# wheelBLE.net
KiCad netlist of a schematic drawn in EAGLE
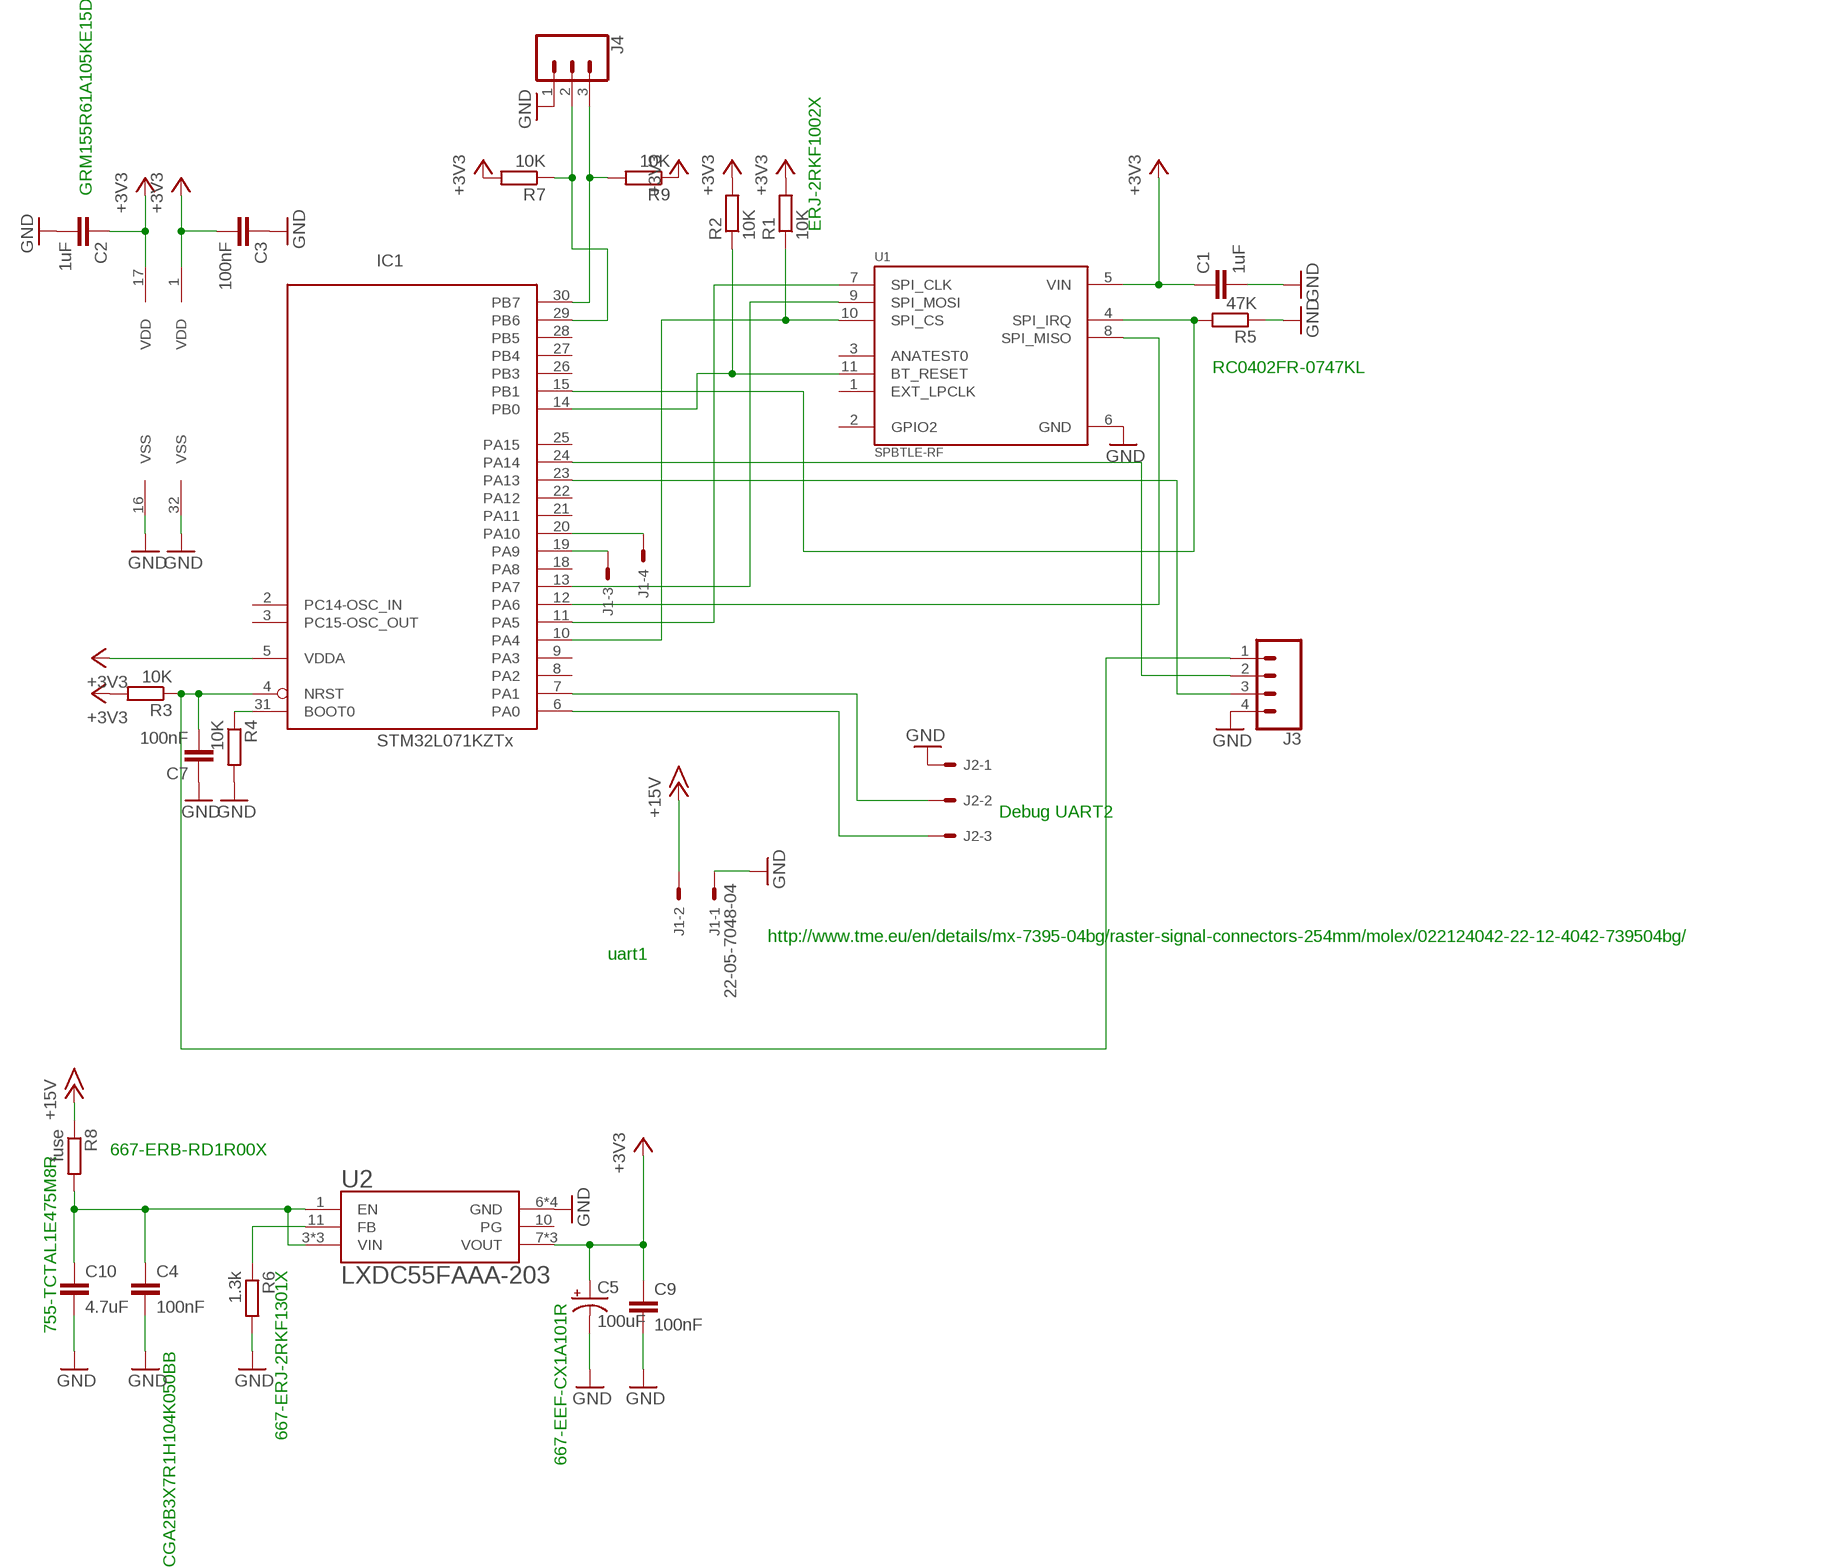
[diagram p0: schematic, sheet 1]

(export (version "E")
  (design (tool "Eeschema 10.0.6"))
  (components
    (comp (ref "C1")
      (value "1uF")
      (footprint "eagle-import:C0402")
      (libsource (lib "eagle-import") (part "C-EUC0402"))
    )
    (comp (ref "C2")
      (value "1uF")
      (footprint "eagle-import:C0402")
      (libsource (lib "eagle-import") (part "C-EUC0402"))
    )
    (comp (ref "C3")
      (value "100nF")
      (footprint "eagle-import:C0402")
      (libsource (lib "eagle-import") (part "C-EUC0402"))
    )
    (comp (ref "C4")
      (value "100nF")
      (footprint "eagle-import:C0402")
      (libsource (lib "eagle-import") (part "C-EUC0402"))
    )
    (comp (ref "C5")
      (value "100uF")
      (footprint "eagle-import:EIA7343")
      (libsource (lib "eagle-import") (part "100UF-POLAR-EIA7343-10V-10%(TANT)"))
    )
    (comp (ref "C7")
      (value "100nF")
      (footprint "eagle-import:C0402")
      (libsource (lib "eagle-import") (part "C-EUC0402"))
    )
    (comp (ref "C9")
      (value "100nF")
      (footprint "eagle-import:C0402")
      (libsource (lib "eagle-import") (part "C-EUC0402"))
    )
    (comp (ref "C10")
      (value "4.7uF")
      (footprint "eagle-import:1206")
      (libsource (lib "eagle-import") (part "4.7UF-1206-16V-(+80/-20%)"))
    )
    (comp (ref "IC1")
      (value "STM32L071KZTx")
      (footprint "eagle-import:LQFP32")
      (libsource (lib "eagle-import") (part "STM32L051KT8"))
    )
    (comp (ref "J1")
      (value "22-05-7048-04")
      (footprint "eagle-import:7395-04")
      (libsource (lib "eagle-import") (part "22-?-0405-7048"))
    )
    (comp (ref "J2")
      (value "22-05-7038-03")
      (footprint "eagle-import:7395-03")
      (libsource (lib "eagle-import") (part "22-?-0305-7038"))
    )
    (comp (ref "J3")
      (value "CONN_04")
      (footprint "eagle-import:1X04")
      (libsource (lib "eagle-import") (part "CONN_04"))
    )
    (comp (ref "J4")
      (value "CONN_03SMD")
      (footprint "eagle-import:1X03-1MM-RA")
      (libsource (lib "eagle-import") (part "CONN_03SMD"))
    )
    (comp (ref "R1")
      (value "10K")
      (footprint "eagle-import:R0402")
      (libsource (lib "eagle-import") (part "R-EU_R0402"))
    )
    (comp (ref "R2")
      (value "10K")
      (footprint "eagle-import:R0402")
      (libsource (lib "eagle-import") (part "R-EU_R0402"))
    )
    (comp (ref "R3")
      (value "10K")
      (footprint "eagle-import:R0402")
      (libsource (lib "eagle-import") (part "R-EU_R0402"))
    )
    (comp (ref "R4")
      (value "10K")
      (footprint "eagle-import:R0402")
      (libsource (lib "eagle-import") (part "R-EU_R0402"))
    )
    (comp (ref "R5")
      (value "47K")
      (footprint "eagle-import:R0402")
      (libsource (lib "eagle-import") (part "R-EU_R0402"))
    )
    (comp (ref "R6")
      (value "1.3k")
      (footprint "eagle-import:R0402")
      (libsource (lib "eagle-import") (part "R-EU_R0402"))
    )
    (comp (ref "R7")
      (value "10K")
      (footprint "eagle-import:R0402")
      (libsource (lib "eagle-import") (part "R-EU_R0402"))
    )
    (comp (ref "R8")
      (value "fuse")
      (footprint "eagle-import:R0402")
      (libsource (lib "eagle-import") (part "R-EU_R0402"))
    )
    (comp (ref "R9")
      (value "10K")
      (footprint "eagle-import:R0402")
      (libsource (lib "eagle-import") (part "R-EU_R0402"))
    )
    (comp (ref "U1")
      (value "SPBTLE-RF")
      (footprint "eagle-import:XCVR_SPBTLE-RF")
      (fields (field (name "MF") "STMicroelectronics"))
      (libsource (lib "eagle-import") (part "SPBTLE-RF"))
    )
    (comp (ref "U2")
      (value "LXDC55FAAA-203")
      (footprint "eagle-import:CONV_LXDC55FAAA-203")
      (fields (field (name "MF") "Murata"))
      (libsource (lib "eagle-import") (part "LXDC55FAAA-203"))
    )
  )
  (nets
    (net (code "1") (name "+3V3") (class "Default")
      (node (ref "C1") (pin "1") (pinfunction "1_1") (pintype "passive"))
      (node (ref "C2") (pin "1") (pinfunction "1_1") (pintype "passive"))
      (node (ref "C3") (pin "2") (pinfunction "2_2") (pintype "passive"))
      (node (ref "C5") (pin "A") (pinfunction "+_A") (pintype "passive"))
      (node (ref "C9") (pin "1") (pinfunction "1_1") (pintype "passive"))
      (node (ref "IC1") (pin "1") (pinfunction "VDD_1") (pintype "power_in"))
      (node (ref "IC1") (pin "17") (pinfunction "VDD_17") (pintype "power_in"))
      (node (ref "IC1") (pin "5") (pinfunction "VDDA_5") (pintype "power_in"))
      (node (ref "R1") (pin "2") (pinfunction "2_2") (pintype "passive"))
      (node (ref "R2") (pin "2") (pinfunction "2_2") (pintype "passive"))
      (node (ref "R3") (pin "2") (pinfunction "2_2") (pintype "passive"))
      (node (ref "R7") (pin "2") (pinfunction "2_2") (pintype "passive"))
      (node (ref "R9") (pin "1") (pinfunction "1_1") (pintype "passive"))
      (node (ref "U1") (pin "5") (pinfunction "VIN_5") (pintype "power_in"))
      (node (ref "U2") (pin "7") (pinfunction "VOUT_7") (pintype "output"))
      (node (ref "U2") (pin "8") (pinfunction "VOUT_8") (pintype "output"))
      (node (ref "U2") (pin "9") (pinfunction "VOUT_9") (pintype "output"))
    )
    (net (code "2") (name "+15V") (class "Default")
      (node (ref "J1") (pin "2") (pinfunction "S_2") (pintype "passive"))
      (node (ref "R8") (pin "1") (pinfunction "1_1") (pintype "passive"))
    )
    (net (code "3") (name "GND") (class "Default")
      (node (ref "C1") (pin "2") (pinfunction "2_2") (pintype "passive"))
      (node (ref "C10") (pin "2") (pinfunction "2_2") (pintype "passive"))
      (node (ref "C2") (pin "2") (pinfunction "2_2") (pintype "passive"))
      (node (ref "C3") (pin "1") (pinfunction "1_1") (pintype "passive"))
      (node (ref "C4") (pin "2") (pinfunction "2_2") (pintype "passive"))
      (node (ref "C5") (pin "C") (pinfunction "-_C") (pintype "passive"))
      (node (ref "C7") (pin "1") (pinfunction "1_1") (pintype "passive"))
      (node (ref "C9") (pin "2") (pinfunction "2_2") (pintype "passive"))
      (node (ref "IC1") (pin "16") (pinfunction "VSS_16") (pintype "power_in"))
      (node (ref "IC1") (pin "32") (pinfunction "VSS_32") (pintype "power_in"))
      (node (ref "J1") (pin "1") (pinfunction "S_1") (pintype "passive"))
      (node (ref "J2") (pin "1") (pinfunction "S_1") (pintype "passive"))
      (node (ref "J3") (pin "4") (pinfunction "4_4") (pintype "passive"))
      (node (ref "J4") (pin "1") (pinfunction "1_1") (pintype "passive"))
      (node (ref "R4") (pin "2") (pinfunction "2_2") (pintype "passive"))
      (node (ref "R5") (pin "1") (pinfunction "1_1") (pintype "passive"))
      (node (ref "R6") (pin "2") (pinfunction "2_2") (pintype "passive"))
      (node (ref "U1") (pin "6") (pinfunction "GND_6") (pintype "power_in"))
      (node (ref "U2") (pin "12") (pinfunction "GND_12") (pintype "power_in"))
      (node (ref "U2") (pin "13") (pinfunction "GND_13") (pintype "power_in"))
      (node (ref "U2") (pin "14") (pinfunction "GND_14") (pintype "power_in"))
      (node (ref "U2") (pin "6") (pinfunction "GND_6") (pintype "power_in"))
    )
    (net (code "4") (name "Net-(IC1A-BOOT0)") (class "Default")
      (node (ref "IC1") (pin "31") (pinfunction "BOOT0_31") (pintype "input"))
      (node (ref "R4") (pin "1") (pinfunction "1_1") (pintype "passive"))
    )
    (net (code "5") (name "Net-(IC1A-NRST)") (class "Default")
      (node (ref "C7") (pin "2") (pinfunction "2_2") (pintype "passive"))
      (node (ref "IC1") (pin "4") (pinfunction "NRST_4") (pintype "bidirectional"))
      (node (ref "J3") (pin "1") (pinfunction "1_1") (pintype "passive"))
      (node (ref "R3") (pin "1") (pinfunction "1_1") (pintype "passive"))
    )
    (net (code "6") (name "Net-(IC1A-PA0)") (class "Default")
      (node (ref "IC1") (pin "6") (pinfunction "PA0_6") (pintype "bidirectional"))
      (node (ref "J2") (pin "3") (pinfunction "S_3") (pintype "passive"))
    )
    (net (code "7") (name "Net-(IC1A-PA1)") (class "Default")
      (node (ref "IC1") (pin "7") (pinfunction "PA1_7") (pintype "bidirectional"))
      (node (ref "J2") (pin "2") (pinfunction "S_2") (pintype "passive"))
    )
    (net (code "8") (name "Net-(IC1A-PA4)") (class "Default")
      (node (ref "IC1") (pin "10") (pinfunction "PA4_10") (pintype "bidirectional"))
      (node (ref "R1") (pin "1") (pinfunction "1_1") (pintype "passive"))
      (node (ref "U1") (pin "10") (pinfunction "SPI_CS_10") (pintype "input"))
    )
    (net (code "9") (name "Net-(IC1A-PA5)") (class "Default")
      (node (ref "IC1") (pin "11") (pinfunction "PA5_11") (pintype "bidirectional"))
      (node (ref "U1") (pin "7") (pinfunction "SPI_CLK_7") (pintype "input"))
    )
    (net (code "10") (name "Net-(IC1A-PA6)") (class "Default")
      (node (ref "IC1") (pin "12") (pinfunction "PA6_12") (pintype "bidirectional"))
      (node (ref "U1") (pin "8") (pinfunction "SPI_MISO_8") (pintype "output"))
    )
    (net (code "11") (name "Net-(IC1A-PA7)") (class "Default")
      (node (ref "IC1") (pin "13") (pinfunction "PA7_13") (pintype "bidirectional"))
      (node (ref "U1") (pin "9") (pinfunction "SPI_MOSI_9") (pintype "input"))
    )
    (net (code "12") (name "Net-(IC1A-PA9)") (class "Default")
      (node (ref "IC1") (pin "19") (pinfunction "PA9_19") (pintype "bidirectional"))
      (node (ref "J1") (pin "3") (pinfunction "S_3") (pintype "passive"))
    )
    (net (code "13") (name "Net-(IC1A-PA10)") (class "Default")
      (node (ref "IC1") (pin "20") (pinfunction "PA10_20") (pintype "bidirectional"))
      (node (ref "J1") (pin "4") (pinfunction "S_4") (pintype "passive"))
    )
    (net (code "14") (name "Net-(IC1A-PA13)") (class "Default")
      (node (ref "IC1") (pin "23") (pinfunction "PA13_23") (pintype "bidirectional"))
      (node (ref "J3") (pin "3") (pinfunction "3_3") (pintype "passive"))
    )
    (net (code "15") (name "Net-(IC1A-PA14)") (class "Default")
      (node (ref "IC1") (pin "24") (pinfunction "PA14_24") (pintype "bidirectional"))
      (node (ref "J3") (pin "2") (pinfunction "2_2") (pintype "passive"))
    )
    (net (code "16") (name "Net-(IC1A-PB0)") (class "Default")
      (node (ref "IC1") (pin "14") (pinfunction "PB0_14") (pintype "bidirectional"))
      (node (ref "R2") (pin "1") (pinfunction "1_1") (pintype "passive"))
      (node (ref "U1") (pin "11") (pinfunction "BT_RESET_11") (pintype "input"))
    )
    (net (code "17") (name "Net-(IC1A-PB1)") (class "Default")
      (node (ref "IC1") (pin "15") (pinfunction "PB1_15") (pintype "bidirectional"))
      (node (ref "R5") (pin "2") (pinfunction "2_2") (pintype "passive"))
      (node (ref "U1") (pin "4") (pinfunction "SPI_IRQ_4") (pintype "output"))
    )
    (net (code "18") (name "Net-(IC1A-PB6)") (class "Default")
      (node (ref "IC1") (pin "29") (pinfunction "PB6_29") (pintype "bidirectional"))
      (node (ref "J4") (pin "2") (pinfunction "2_2") (pintype "passive"))
      (node (ref "R7") (pin "1") (pinfunction "1_1") (pintype "passive"))
    )
    (net (code "19") (name "Net-(IC1A-PB7)") (class "Default")
      (node (ref "IC1") (pin "30") (pinfunction "PB7_30") (pintype "bidirectional"))
      (node (ref "J4") (pin "3") (pinfunction "3_3") (pintype "passive"))
      (node (ref "R9") (pin "2") (pinfunction "2_2") (pintype "passive"))
    )
    (net (code "20") (name "Net-(U2-EN)") (class "Default")
      (node (ref "C10") (pin "1") (pinfunction "1_1") (pintype "passive"))
      (node (ref "C4") (pin "1") (pinfunction "1_1") (pintype "passive"))
      (node (ref "R8") (pin "2") (pinfunction "2_2") (pintype "passive"))
      (node (ref "U2") (pin "1") (pinfunction "EN_1") (pintype "input"))
      (node (ref "U2") (pin "3") (pinfunction "VIN_3") (pintype "input"))
      (node (ref "U2") (pin "4") (pinfunction "VIN_4") (pintype "input"))
      (node (ref "U2") (pin "5") (pinfunction "VIN_5") (pintype "input"))
    )
    (net (code "21") (name "Net-(U2-FB)") (class "Default")
      (node (ref "R6") (pin "1") (pinfunction "1_1") (pintype "passive"))
      (node (ref "U2") (pin "11") (pinfunction "FB_11") (pintype "input"))
    )
    (net (code "22") (name "unconnected-(IC1A-PA2-Pad8)") (class "Default")
      (node (ref "IC1") (pin "8") (pinfunction "PA2_8") (pintype "bidirectional"))
    )
    (net (code "23") (name "unconnected-(IC1A-PA3-Pad9)") (class "Default")
      (node (ref "IC1") (pin "9") (pinfunction "PA3_9") (pintype "bidirectional"))
    )
    (net (code "24") (name "unconnected-(IC1A-PA8-Pad18)") (class "Default")
      (node (ref "IC1") (pin "18") (pinfunction "PA8_18") (pintype "bidirectional"))
    )
    (net (code "25") (name "unconnected-(IC1A-PA11-Pad21)") (class "Default")
      (node (ref "IC1") (pin "21") (pinfunction "PA11_21") (pintype "bidirectional"))
    )
    (net (code "26") (name "unconnected-(IC1A-PA12-Pad22)") (class "Default")
      (node (ref "IC1") (pin "22") (pinfunction "PA12_22") (pintype "bidirectional"))
    )
    (net (code "27") (name "unconnected-(IC1A-PA15-Pad25)") (class "Default")
      (node (ref "IC1") (pin "25") (pinfunction "PA15_25") (pintype "bidirectional"))
    )
    (net (code "28") (name "unconnected-(IC1A-PB3-Pad26)") (class "Default")
      (node (ref "IC1") (pin "26") (pinfunction "PB3_26") (pintype "bidirectional"))
    )
    (net (code "29") (name "unconnected-(IC1A-PB4-Pad27)") (class "Default")
      (node (ref "IC1") (pin "27") (pinfunction "PB4_27") (pintype "bidirectional"))
    )
    (net (code "30") (name "unconnected-(IC1A-PB5-Pad28)") (class "Default")
      (node (ref "IC1") (pin "28") (pinfunction "PB5_28") (pintype "bidirectional"))
    )
    (net (code "31") (name "unconnected-(IC1A-PC14-OSC_IN-Pad2)") (class "Default")
      (node (ref "IC1") (pin "2") (pinfunction "PC14-OSC_IN_2") (pintype "bidirectional"))
    )
    (net (code "32") (name "unconnected-(IC1A-PC15-OSC_OUT-Pad3)") (class "Default")
      (node (ref "IC1") (pin "3") (pinfunction "PC15-OSC_OUT_3") (pintype "bidirectional"))
    )
    (net (code "33") (name "unconnected-(U1-ANATEST0-Pad3)") (class "Default")
      (node (ref "U1") (pin "3") (pinfunction "ANATEST0_3") (pintype "input"))
    )
    (net (code "34") (name "unconnected-(U1-EXT_LPCLK-Pad1)") (class "Default")
      (node (ref "U1") (pin "1") (pinfunction "EXT_LPCLK_1") (pintype "input"))
    )
    (net (code "35") (name "unconnected-(U1-GPIO2-Pad2)") (class "Default")
      (node (ref "U1") (pin "2") (pinfunction "GPIO2_2") (pintype "bidirectional"))
    )
    (net (code "36") (name "unconnected-(U2-PG-Pad10)") (class "Default")
      (node (ref "U2") (pin "10") (pinfunction "PG_10") (pintype "output"))
    )
  )
)
